# AutoLevel_Module_V1.net
KiCad netlist of a schematic drawn in EAGLE
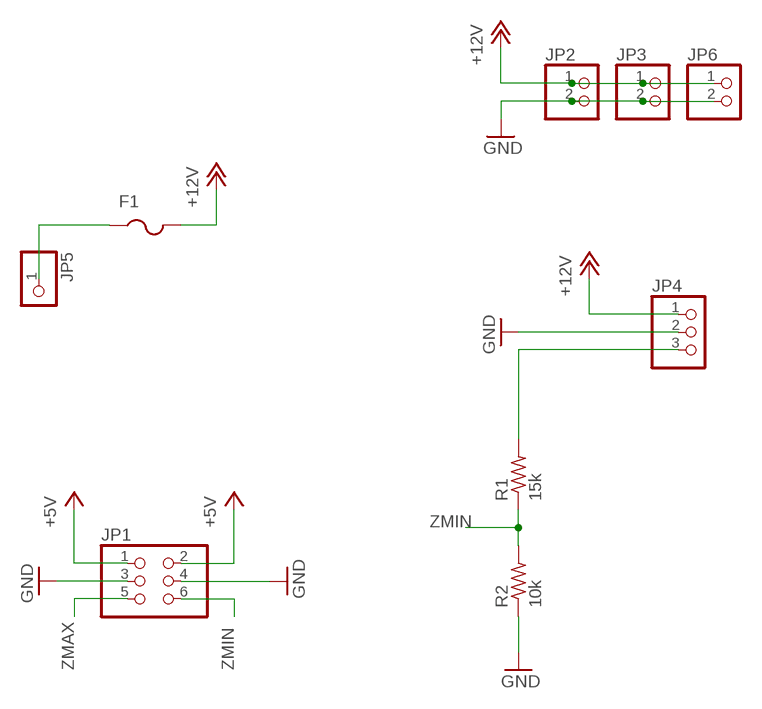
[diagram p0: schematic, sheet 1]

(export (version "E")
  (design (tool "Eeschema 10.0.6"))
  (components
    (comp (ref "F1")
      (value "PTCFUSE-1812")
      (footprint "eagle-import:1812")
      (libsource (lib "eagle-import") (part "PTCFUSE-1812"))
    )
    (comp (ref "JP1")
      (value "PINHD-2X3")
      (footprint "eagle-import:2X03")
      (libsource (lib "eagle-import") (part "PINHD-2X3"))
    )
    (comp (ref "JP2")
      (value "PINHD-1X2")
      (footprint "eagle-import:1X02")
      (libsource (lib "eagle-import") (part "PINHD-1X2"))
    )
    (comp (ref "JP3")
      (value "PINHD-1X2")
      (footprint "eagle-import:1X02")
      (libsource (lib "eagle-import") (part "PINHD-1X2"))
    )
    (comp (ref "JP4")
      (value "PINHD-1X3")
      (footprint "eagle-import:1X03")
      (libsource (lib "eagle-import") (part "PINHD-1X3"))
    )
    (comp (ref "JP5")
      (value "PINHD-1X1")
      (footprint "eagle-import:1X01")
      (libsource (lib "eagle-import") (part "PINHD-1X1"))
    )
    (comp (ref "JP6")
      (value "PINHD-1X2")
      (footprint "eagle-import:1X02")
      (libsource (lib "eagle-import") (part "PINHD-1X2"))
    )
    (comp (ref "R1")
      (value "15k")
      (footprint "eagle-import:R0805")
      (libsource (lib "eagle-import") (part "R-US_R0805"))
    )
    (comp (ref "R2")
      (value "10k")
      (footprint "eagle-import:R0805")
      (libsource (lib "eagle-import") (part "R-US_R0805"))
    )
  )
  (nets
    (net (code "1") (name "+5V") (class "Default")
      (node (ref "JP1") (pin "1") (pinfunction "1_1") (pintype "passive"))
      (node (ref "JP1") (pin "2") (pinfunction "2_2") (pintype "passive"))
    )
    (net (code "2") (name "+12V") (class "Default")
      (node (ref "F1") (pin "2") (pinfunction "2_2") (pintype "passive"))
      (node (ref "JP2") (pin "1") (pinfunction "1_1") (pintype "passive"))
      (node (ref "JP3") (pin "1") (pinfunction "1_1") (pintype "passive"))
      (node (ref "JP4") (pin "1") (pinfunction "1_1") (pintype "passive"))
      (node (ref "JP6") (pin "1") (pinfunction "1_1") (pintype "passive"))
    )
    (net (code "3") (name "/ZMAX") (class "Default")
      (node (ref "JP1") (pin "5") (pinfunction "5_5") (pintype "passive"))
    )
    (net (code "4") (name "/ZMIN") (class "Default")
      (node (ref "JP1") (pin "6") (pinfunction "6_6") (pintype "passive"))
      (node (ref "R1") (pin "1") (pinfunction "1_1") (pintype "passive"))
      (node (ref "R2") (pin "2") (pinfunction "2_2") (pintype "passive"))
    )
    (net (code "5") (name "GND") (class "Default")
      (node (ref "JP1") (pin "3") (pinfunction "3_3") (pintype "passive"))
      (node (ref "JP1") (pin "4") (pinfunction "4_4") (pintype "passive"))
      (node (ref "JP2") (pin "2") (pinfunction "2_2") (pintype "passive"))
      (node (ref "JP3") (pin "2") (pinfunction "2_2") (pintype "passive"))
      (node (ref "JP4") (pin "2") (pinfunction "2_2") (pintype "passive"))
      (node (ref "JP6") (pin "2") (pinfunction "2_2") (pintype "passive"))
      (node (ref "R2") (pin "1") (pinfunction "1_1") (pintype "passive"))
    )
    (net (code "6") (name "Net-(F1-Pad1)") (class "Default")
      (node (ref "F1") (pin "1") (pinfunction "1_1") (pintype "passive"))
      (node (ref "JP5") (pin "1") (pinfunction "1_1") (pintype "passive"))
    )
    (net (code "7") (name "Net-(JP4-Pad3)") (class "Default")
      (node (ref "JP4") (pin "3") (pinfunction "3_3") (pintype "passive"))
      (node (ref "R1") (pin "2") (pinfunction "2_2") (pintype "passive"))
    )
  )
)
